# design.net
KiCad netlist of a schematic drawn in Altium Designer
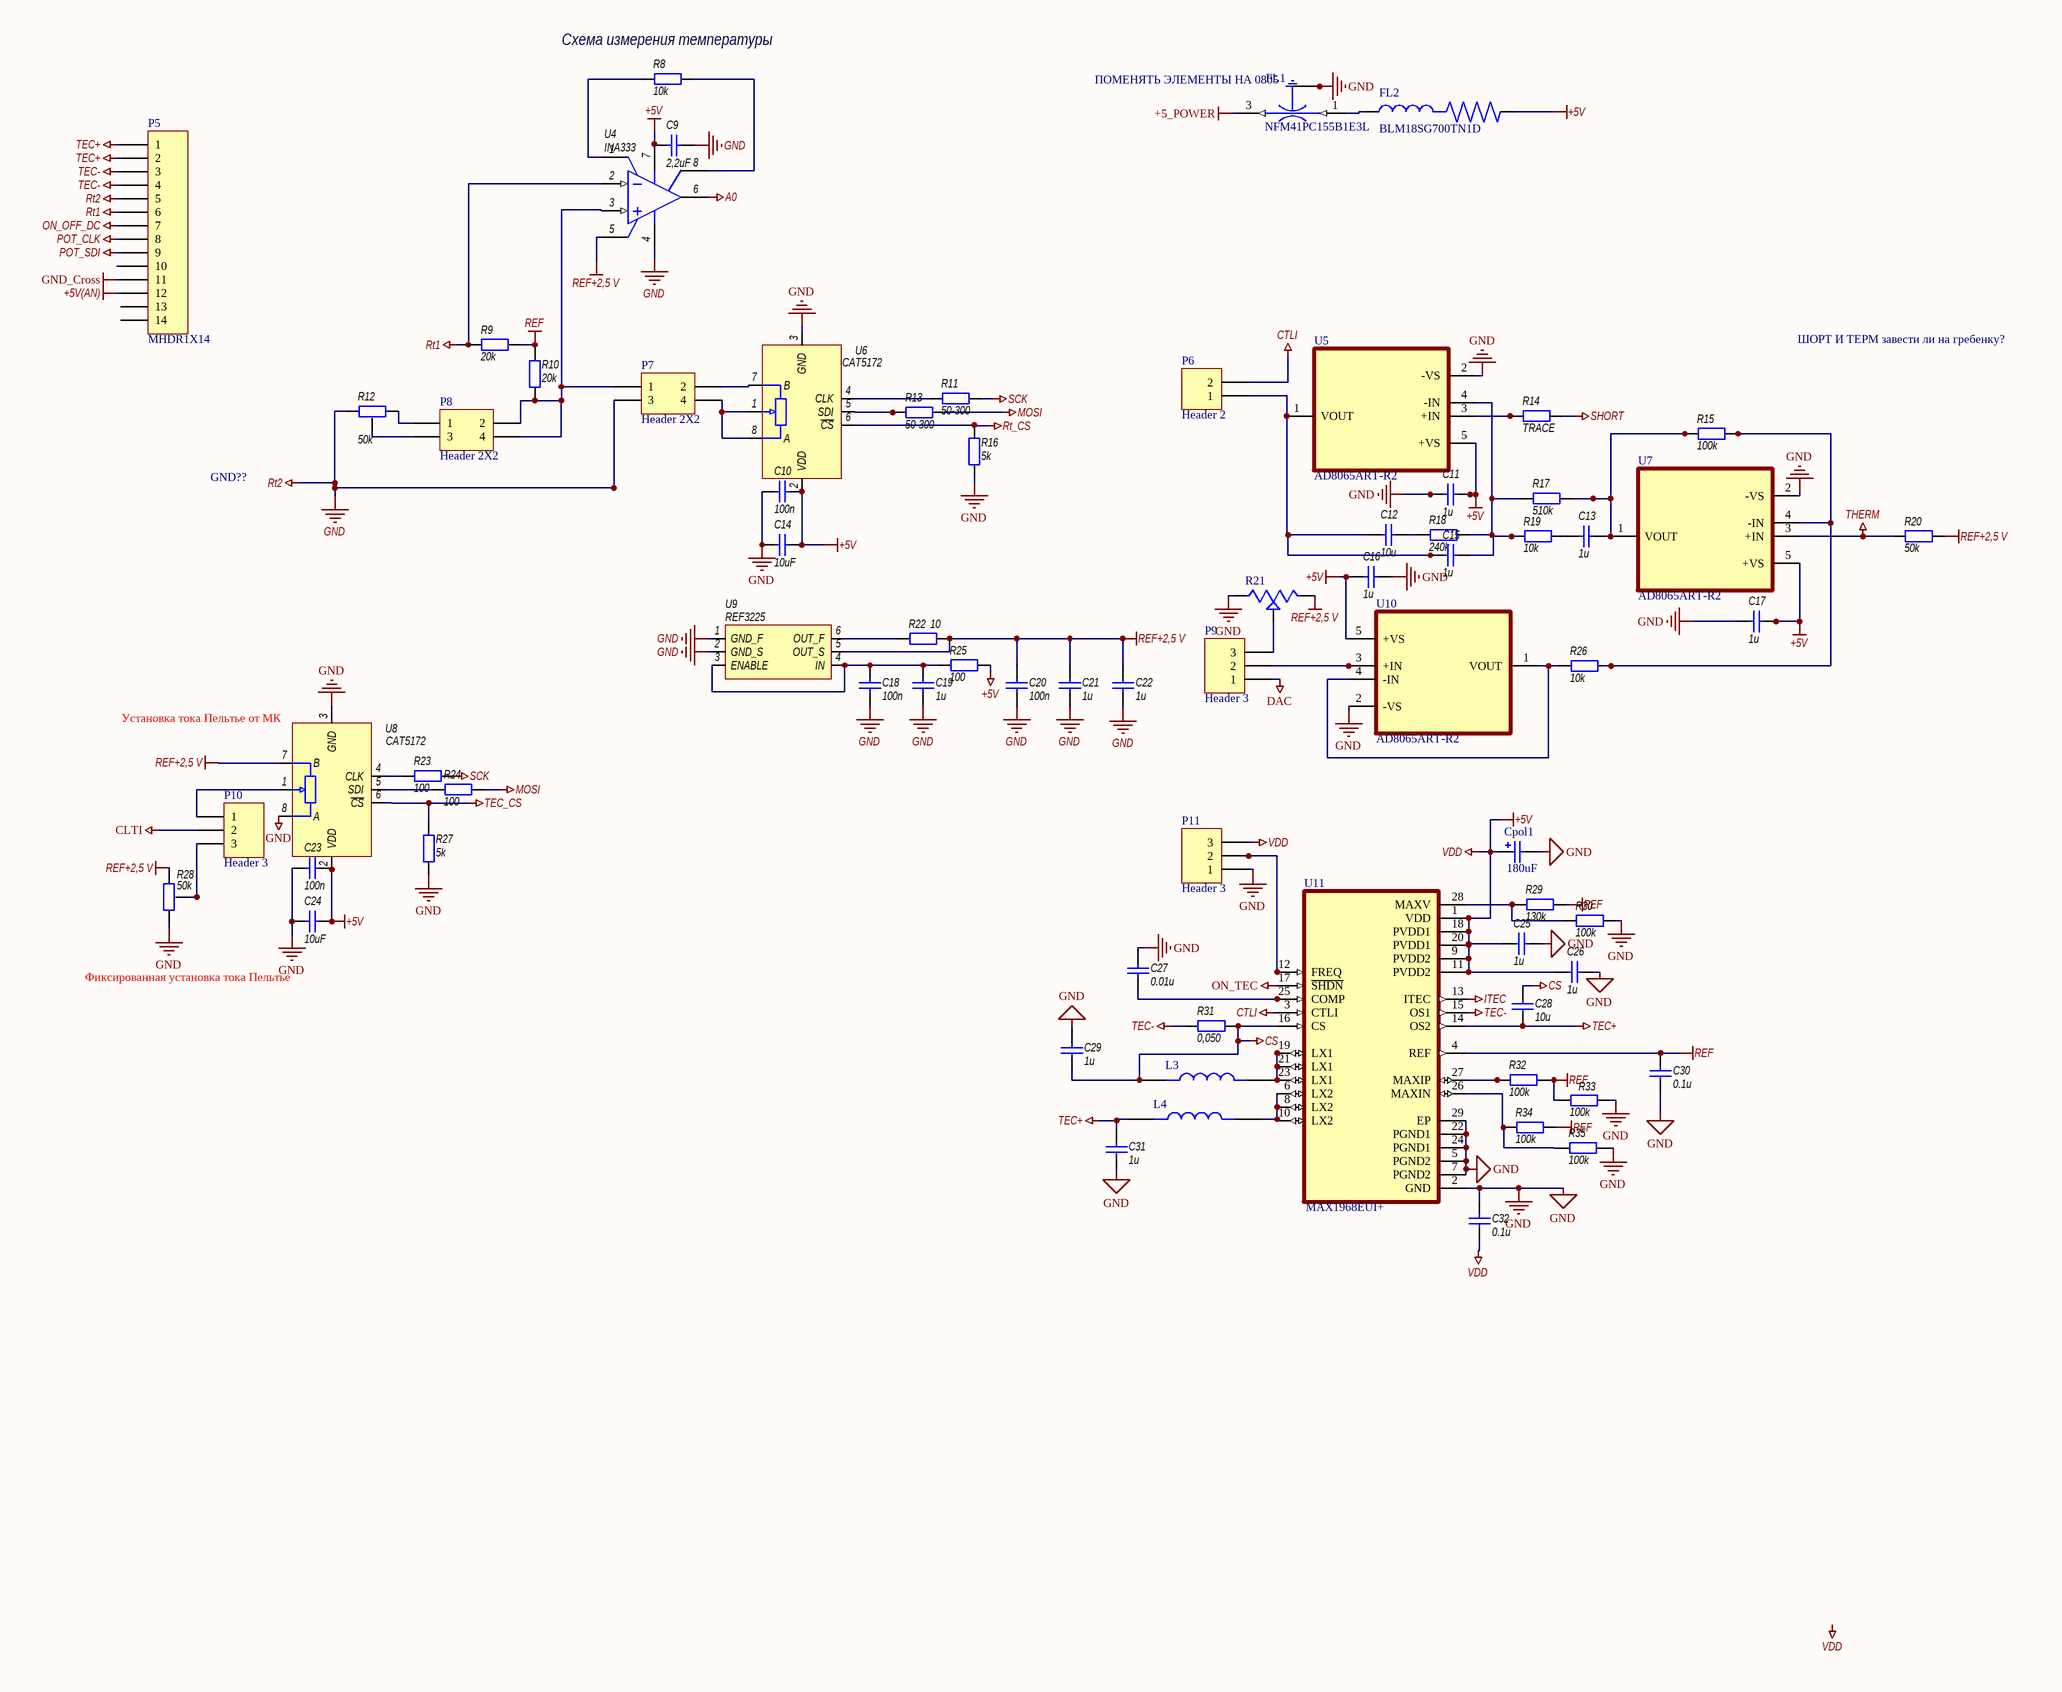
[diagram p0: схема платы пельтье.SchDoc]

(export (version "E")
  (design (tool "Eeschema 10.0.6"))
  (components
    (comp (ref "C9") (value "2,2uF") (footprint "0603") (libsource (lib "my-lib") (part "_capacitor")))
    (comp (ref "C10") (value "100n") (footprint "0603") (libsource (lib "my-lib") (part "_capacitor")))
    (comp (ref "C11") (value "1u") (footprint "0603") (libsource (lib "my-lib") (part "_capacitor")))
    (comp (ref "C12") (value "10u") (footprint "0603") (libsource (lib "my-lib") (part "_capacitor")))
    (comp (ref "C13") (value "1u") (footprint "0603") (libsource (lib "my-lib") (part "_capacitor")))
    (comp (ref "C14") (value "10uF") (footprint "0603") (libsource (lib "my-lib") (part "_capacitor")))
    (comp (ref "C15") (value "1u") (footprint "0603") (libsource (lib "my-lib") (part "_capacitor")))
    (comp (ref "C16") (value "1u") (footprint "0603") (libsource (lib "my-lib") (part "_capacitor")))
    (comp (ref "C17") (value "1u") (footprint "0603") (libsource (lib "my-lib") (part "_capacitor")))
    (comp (ref "C18") (value "100n") (footprint "0603") (libsource (lib "my-lib") (part "_capacitor")))
    (comp (ref "C19") (value "1u") (footprint "0603") (libsource (lib "my-lib") (part "_capacitor")))
    (comp (ref "C20") (value "100n") (footprint "0603") (libsource (lib "my-lib") (part "_capacitor")))
    (comp (ref "C21") (value "1u") (footprint "0603") (libsource (lib "my-lib") (part "_capacitor")))
    (comp (ref "C22") (value "1u") (footprint "0603") (libsource (lib "my-lib") (part "_capacitor")))
    (comp (ref "C23") (value "100n") (footprint "0603") (libsource (lib "my-lib") (part "_capacitor")))
    (comp (ref "C24") (value "10uF") (footprint "0603") (libsource (lib "my-lib") (part "_capacitor")))
    (comp (ref "C25") (value "1u") (footprint "0603") (libsource (lib "my-lib") (part "_capacitor")))
    (comp (ref "C26") (value "1u") (footprint "0603") (libsource (lib "my-lib") (part "_capacitor")))
    (comp (ref "C27") (value "0.01u") (footprint "0603") (libsource (lib "my-lib") (part "_capacitor")))
    (comp (ref "C28") (value "10u") (footprint "0603") (libsource (lib "my-lib") (part "_capacitor")))
    (comp (ref "C29") (value "1u") (footprint "0603") (libsource (lib "my-lib") (part "_capacitor")))
    (comp (ref "C30") (value "0.1u") (footprint "0603") (libsource (lib "my-lib") (part "_capacitor")))
    (comp (ref "C31") (value "1u") (footprint "0603") (libsource (lib "my-lib") (part "_capacitor")))
    (comp (ref "C32") (value "0.1u") (footprint "0603") (libsource (lib "my-lib") (part "_capacitor")))
    (comp (ref "Cpol1")
      (value "180uF")
      (footprint "CAPPM7343X310N")
      (description "Polarized Capacitor (Axial)")
      (fields (field (name "PUBLISHER") "Altium Limited"))
      (libsource (lib "Miscellaneous Devices") (part "Cap Pol2"))
    )
    (comp (ref "FL1")
      (value "NFM41PC155B1E3L")
      (footprint "FIL_NFM41PC155B1E3L")
      (fields (field (name "MF") "Murata"))
      (libsource (lib "NFM41PC155B1E3L") (part "NFM41PC155B1E3L"))
    )
    (comp (ref "FL2")
      (value "BLM18SG700TN1D")
      (footprint "BEADC2012X105N")
      (fields (field (name "MF") "Murata") (field (name "MP") "BLM21SP111SN1D"))
      (libsource (lib "BLM21SP111SN1D") (part "BLM21SP111SN1D"))
    )
    (comp (ref "L3")
      (value "~")
      (footprint "IHLP")
      (description "Ð˜Ð½Ð´ÑƒÐºÑ‚Ð¾Ñ€ Ñ Ð¸Ð½Ð´ÑƒÐºÑ‚Ð¸Ð²Ð½Ð¾ÑÑ‚ÑŒÑŽ: 3,3 uH Tol. + / -30%, Ð¿Ð°ÐºÐµÑ‚: 2020 (5050)")
      (fields (field (name "MF") "Murata") (field (name "MP") "LQH5BPN3R3NT0L"))
      (libsource (lib "LQH5BPN3R3NT0L") (part "LQH5BPN3R3NT0L"))
    )
    (comp (ref "L4")
      (value "~")
      (footprint "IHLP")
      (description "Ð˜Ð½Ð´ÑƒÐºÑ‚Ð¾Ñ€ Ñ Ð¸Ð½Ð´ÑƒÐºÑ‚Ð¸Ð²Ð½Ð¾ÑÑ‚ÑŒÑŽ: 3,3 uH Tol. + / -30%, Ð¿Ð°ÐºÐµÑ‚: 2020 (5050)")
      (fields (field (name "MF") "Murata") (field (name "MP") "LQH5BPN3R3NT0L"))
      (libsource (lib "LQH5BPN3R3NT0L") (part "LQH5BPN3R3NT0L"))
    )
    (comp (ref "P5")
      (value "MHDR1X14")
      (footprint "HDR1X14")
      (description "Header, 14-Pin")
      (fields (field (name "PUBLISHER") "Altium Limited"))
      (libsource (lib "Miscellaneous Connectors") (part "MHDR1X14"))
    )
    (comp (ref "P6")
      (value "Header 2")
      (footprint "HDR1X2")
      (description "Header, 2-Pin")
      (fields (field (name "PUBLISHER") "Altium Limited"))
      (libsource (lib "Miscellaneous Connectors") (part "Header 2"))
    )
    (comp (ref "P7")
      (value "Header 2X2")
      (footprint "HDR2X2")
      (description "Header, 2-Pin, Dual row")
      (fields (field (name "PUBLISHER") "Altium Limited"))
      (libsource (lib "Miscellaneous Connectors") (part "Header 2X2"))
    )
    (comp (ref "P8")
      (value "Header 2X2")
      (footprint "HDR2X2")
      (description "Header, 2-Pin, Dual row")
      (fields (field (name "PUBLISHER") "Altium Limited"))
      (libsource (lib "Miscellaneous Connectors") (part "Header 2X2"))
    )
    (comp (ref "P9")
      (value "Header 3")
      (footprint "HDR1X3")
      (description "Header, 3-Pin")
      (fields (field (name "PUBLISHER") "Altium Limited"))
      (libsource (lib "Miscellaneous Connectors") (part "Header 3"))
    )
    (comp (ref "P10")
      (value "Header 3")
      (footprint "HDR1X3")
      (description "Header, 3-Pin")
      (fields (field (name "PUBLISHER") "Altium Limited"))
      (libsource (lib "") (part "Header 3_1"))
    )
    (comp (ref "P11")
      (value "Header 3")
      (footprint "HDR1X3")
      (description "Header, 3-Pin")
      (fields (field (name "PUBLISHER") "Altium Limited"))
      (libsource (lib "Miscellaneous Connectors") (part "Header 3"))
    )
    (comp (ref "R8") (value "10k") (footprint "0603") (libsource (lib "my-lib") (part "_resistor")))
    (comp (ref "R9") (value "20k") (footprint "0603") (libsource (lib "my-lib") (part "_resistor")))
    (comp (ref "R10") (value "20k") (footprint "0603") (libsource (lib "my-lib") (part "_resistor")))
    (comp (ref "R11") (value "50-300") (footprint "0603") (libsource (lib "my-lib") (part "_resistor")))
    (comp (ref "R12")
      (value "50k")
      (footprint "TRIM_3296X-1-203LF")
      (description "3224J")
      (libsource (lib "my-lib") (part "_resistor_pot"))
    )
    (comp (ref "R13") (value "50-300") (footprint "0603") (libsource (lib "my-lib") (part "_resistor")))
    (comp (ref "R14") (value "TRACE") (footprint "0603") (libsource (lib "my-lib") (part "_resistor")))
    (comp (ref "R15") (value "100k") (footprint "0603") (libsource (lib "my-lib") (part "_resistor")))
    (comp (ref "R16") (value "5k") (footprint "0603") (libsource (lib "my-lib") (part "_resistor")))
    (comp (ref "R17") (value "510k") (footprint "0603") (libsource (lib "my-lib") (part "_resistor")))
    (comp (ref "R18") (value "240k") (footprint "0603") (libsource (lib "my-lib") (part "_resistor")))
    (comp (ref "R19") (value "10k") (footprint "0603") (libsource (lib "my-lib") (part "_resistor")))
    (comp (ref "R20") (value "50k") (footprint "0603") (libsource (lib "my-lib") (part "_resistor")))
    (comp (ref "R21")
      (value "~")
      (footprint "TRIM_3296X-1-203LF")
      (description "Trimmer Resistors - Through Hole")
      (fields (field (name "MP") "3296W-1-224LF") (field (name "MF") "Bourns"))
      (libsource (lib "3296W-1-224LF") (part "3296W-1-224LF"))
    )
    (comp (ref "R22") (value "10") (footprint "0603") (libsource (lib "my-lib") (part "_resistor")))
    (comp (ref "R23") (value "100") (footprint "0603") (libsource (lib "my-lib") (part "_resistor")))
    (comp (ref "R24") (value "100") (footprint "0603") (libsource (lib "my-lib") (part "_resistor")))
    (comp (ref "R25") (value "100") (footprint "0603") (libsource (lib "my-lib") (part "_resistor")))
    (comp (ref "R26") (value "10k") (footprint "0603") (libsource (lib "my-lib") (part "_resistor")))
    (comp (ref "R27") (value "5k") (footprint "0603") (libsource (lib "my-lib") (part "_resistor")))
    (comp (ref "R28")
      (value "50k")
      (footprint "TRIM_3296X-1-203LF")
      (description "3224J")
      (libsource (lib "my-lib") (part "_resistor_pot"))
    )
    (comp (ref "R29") (value "130k") (footprint "0603") (libsource (lib "my-lib") (part "_resistor")))
    (comp (ref "R30") (value "100k") (footprint "0603") (libsource (lib "my-lib") (part "_resistor")))
    (comp (ref "R31")
      (value "0,050")
      (footprint "RESC3216X65N")
      (libsource (lib "my-lib") (part "_resistor"))
    )
    (comp (ref "R32") (value "100k") (footprint "0603") (libsource (lib "my-lib") (part "_resistor")))
    (comp (ref "R33") (value "100k") (footprint "0603") (libsource (lib "my-lib") (part "_resistor")))
    (comp (ref "R34") (value "100k") (footprint "0603") (libsource (lib "my-lib") (part "_resistor")))
    (comp (ref "R35") (value "100k") (footprint "0603") (libsource (lib "my-lib") (part "_resistor")))
    (comp (ref "U4")
      (value "INA333")
      (footprint "SOP65P490X110-8N")
      (libsource (lib "my-lib") (part "INA333"))
    )
    (comp (ref "U5")
      (value "AD8065ART-R2")
      (footprint "SOT95P290X145-5N")
      (fields (field (name "MF") "Analog Devices"))
      (libsource (lib "AD8065ART-R2") (part "AD8065ART-R2"))
    )
    (comp (ref "U6")
      (value "CAT5172")
      (footprint "SOT65P280X100-8N")
      (description "Digital potentiometr 256-position SPI")
      (libsource (lib "my-lib") (part "CAT5172"))
    )
    (comp (ref "U7")
      (value "AD8065ART-R2")
      (footprint "SOT95P290X145-5N")
      (fields (field (name "MF") "Analog Devices"))
      (libsource (lib "AD8065ART-R2") (part "AD8065ART-R2"))
    )
    (comp (ref "U8")
      (value "CAT5172")
      (footprint "SOT65P280X100-8N")
      (description "Digital potentiometr 256-position SPI")
      (libsource (lib "my-lib") (part "CAT5172"))
    )
    (comp (ref "U9")
      (value "REF3225")
      (footprint "SOT23-6")
      (description "SERIES VOLTAGE REFERENCE")
      (libsource (lib "my-lib") (part "REF32XX"))
    )
    (comp (ref "U10")
      (value "AD8065ART-R2")
      (footprint "SOT95P290X145-5N")
      (fields (field (name "MF") "Analog Devices"))
      (libsource (lib "") (part "AD8065ART-R2_1"))
    )
    (comp (ref "U11")
      (value "MAX1968EUI+")
      (footprint "SOP65P637X110-29N")
      (description "Thermoelectric Cooler PMIC 28-TSSOP-EP")
      (fields (field (name "MF") "Maxim Integrated"))
      (libsource (lib "MAX1968EUI_") (part "MAX1968EUI+"))
    )
  )
  (nets
    (net (code "1") (name "+5V") (class "Default")
      (node (ref "C10") (pin "2") (pinfunction "2_2") (pintype "passive"))
      (node (ref "C11") (pin "2") (pinfunction "2_2") (pintype "passive"))
      (node (ref "C14") (pin "2") (pinfunction "2_2") (pintype "passive"))
      (node (ref "C16") (pin "1") (pinfunction "1_1") (pintype "passive"))
      (node (ref "C17") (pin "2") (pinfunction "2_2") (pintype "passive"))
      (node (ref "C23") (pin "2") (pinfunction "2_2") (pintype "passive"))
      (node (ref "C24") (pin "2") (pinfunction "2_2") (pintype "passive"))
      (node (ref "C25") (pin "1") (pinfunction "1_1") (pintype "passive"))
      (node (ref "C26") (pin "1") (pinfunction "1_1") (pintype "passive"))
      (node (ref "C32") (pin "2") (pinfunction "2_2") (pintype "passive"))
      (node (ref "C9") (pin "2") (pinfunction "2_2") (pintype "passive"))
      (node (ref "Cpol1") (pin "1") (pinfunction "1_1") (pintype "passive"))
      (node (ref "FL2") (pin "2") (pinfunction "2_2") (pintype "passive"))
      (node (ref "P11") (pin "3") (pinfunction "3_3") (pintype "passive"))
      (node (ref "R25") (pin "2") (pinfunction "2_2") (pintype "passive"))
      (node (ref "U10") (pin "5") (pinfunction "+VS_5") (pintype "power_in"))
      (node (ref "U11") (pin "1") (pinfunction "VDD_1") (pintype "power_in"))
      (node (ref "U11") (pin "11") (pinfunction "PVDD2_11") (pintype "power_in"))
      (node (ref "U11") (pin "18") (pinfunction "PVDD1_18") (pintype "power_in"))
      (node (ref "U11") (pin "20") (pinfunction "PVDD1_20") (pintype "power_in"))
      (node (ref "U11") (pin "9") (pinfunction "PVDD2_9") (pintype "power_in"))
      (node (ref "U4") (pin "7") (pinfunction "V+_7") (pintype "power_in"))
      (node (ref "U5") (pin "5") (pinfunction "+VS_5") (pintype "power_in"))
      (node (ref "U6") (pin "2") (pinfunction "VDD_2") (pintype "passive"))
      (node (ref "U7") (pin "5") (pinfunction "+VS_5") (pintype "power_in"))
      (node (ref "U8") (pin "2") (pinfunction "VDD_2") (pintype "passive"))
    )
    (net (code "2") (name "+5V(AN)") (class "Default")
      (node (ref "P5") (pin "12") (pinfunction "12_12") (pintype "passive"))
    )
    (net (code "3") (name "+5_POWER") (class "Default")
      (node (ref "FL1") (pin "3") (pinfunction "OUT_3") (pintype "output"))
    )
    (net (code "4") (name "A0") (class "Default")
      (node (ref "U4") (pin "6") (pinfunction "OUT_6") (pintype "open_collector"))
    )
    (net (code "5") (name "CLTI") (class "Default")
      (node (ref "P10") (pin "2") (pinfunction "2_2") (pintype "passive"))
    )
    (net (code "6") (name "CS") (class "Default")
      (node (ref "C28") (pin "1") (pinfunction "1_1") (pintype "passive"))
      (node (ref "C29") (pin "2") (pinfunction "2_2") (pintype "passive"))
      (node (ref "L3") (pin "1") (pinfunction "1_1") (pintype "passive"))
      (node (ref "R31") (pin "2") (pinfunction "2_2") (pintype "passive"))
      (node (ref "U11") (pin "16") (pinfunction "CS_16") (pintype "input"))
    )
    (net (code "7") (name "CTLI") (class "Default")
      (node (ref "P6") (pin "2") (pinfunction "2_2") (pintype "passive"))
      (node (ref "U11") (pin "3") (pinfunction "CTLI_3") (pintype "input"))
    )
    (net (code "8") (name "DAC") (class "Default")
      (node (ref "P9") (pin "1") (pinfunction "1_1") (pintype "passive"))
    )
    (net (code "9") (name "GND") (class "Default")
      (node (ref "C10") (pin "1") (pinfunction "1_1") (pintype "passive"))
      (node (ref "C11") (pin "1") (pinfunction "1_1") (pintype "passive"))
      (node (ref "C14") (pin "1") (pinfunction "1_1") (pintype "passive"))
      (node (ref "C16") (pin "2") (pinfunction "2_2") (pintype "passive"))
      (node (ref "C17") (pin "1") (pinfunction "1_1") (pintype "passive"))
      (node (ref "C18") (pin "2") (pinfunction "2_2") (pintype "passive"))
      (node (ref "C19") (pin "2") (pinfunction "2_2") (pintype "passive"))
      (node (ref "C20") (pin "2") (pinfunction "2_2") (pintype "passive"))
      (node (ref "C21") (pin "2") (pinfunction "2_2") (pintype "passive"))
      (node (ref "C22") (pin "2") (pinfunction "2_2") (pintype "passive"))
      (node (ref "C23") (pin "1") (pinfunction "1_1") (pintype "passive"))
      (node (ref "C24") (pin "1") (pinfunction "1_1") (pintype "passive"))
      (node (ref "C25") (pin "2") (pinfunction "2_2") (pintype "passive"))
      (node (ref "C26") (pin "2") (pinfunction "2_2") (pintype "passive"))
      (node (ref "C27") (pin "1") (pinfunction "1_1") (pintype "passive"))
      (node (ref "C29") (pin "1") (pinfunction "1_1") (pintype "passive"))
      (node (ref "C30") (pin "2") (pinfunction "2_2") (pintype "passive"))
      (node (ref "C31") (pin "2") (pinfunction "2_2") (pintype "passive"))
      (node (ref "C32") (pin "1") (pinfunction "1_1") (pintype "passive"))
      (node (ref "C9") (pin "1") (pinfunction "1_1") (pintype "passive"))
      (node (ref "Cpol1") (pin "2") (pinfunction "2_2") (pintype "passive"))
      (node (ref "FL1") (pin "2") (pinfunction "GND_2") (pintype "power_in"))
      (node (ref "FL1") (pin "2_1") (pinfunction "GND_2_1") (pintype "power_in"))
      (node (ref "FL1") (pin "2_3") (pinfunction "GND_2_3") (pintype "power_in"))
      (node (ref "FL1") (pin "2_4") (pinfunction "GND_2_4") (pintype "power_in"))
      (node (ref "P11") (pin "1") (pinfunction "1_1") (pintype "passive"))
      (node (ref "P5") (pin "5") (pinfunction "5_5") (pintype "passive"))
      (node (ref "P7") (pin "3") (pinfunction "3_3") (pintype "passive"))
      (node (ref "R12") (pin "3") (pinfunction "3_3") (pintype "passive"))
      (node (ref "R16") (pin "1") (pinfunction "1_1") (pintype "passive"))
      (node (ref "R21") (pin "1") (pinfunction "CCW_1") (pintype "passive"))
      (node (ref "R27") (pin "1") (pinfunction "1_1") (pintype "passive"))
      (node (ref "R28") (pin "3") (pinfunction "3_3") (pintype "passive"))
      (node (ref "R30") (pin "2") (pinfunction "2_2") (pintype "passive"))
      (node (ref "R33") (pin "2") (pinfunction "2_2") (pintype "passive"))
      (node (ref "R35") (pin "2") (pinfunction "2_2") (pintype "passive"))
      (node (ref "U10") (pin "2") (pinfunction "-VS_2") (pintype "power_in"))
      (node (ref "U11") (pin "2") (pinfunction "GND_2") (pintype "power_in"))
      (node (ref "U11") (pin "22") (pinfunction "PGND1_22") (pintype "power_in"))
      (node (ref "U11") (pin "24") (pinfunction "PGND1_24") (pintype "power_in"))
      (node (ref "U11") (pin "29") (pinfunction "EP_29") (pintype "passive"))
      (node (ref "U11") (pin "5") (pinfunction "PGND2_5") (pintype "power_in"))
      (node (ref "U11") (pin "7") (pinfunction "PGND2_7") (pintype "power_in"))
      (node (ref "U4") (pin "4") (pinfunction "V-_4") (pintype "power_in"))
      (node (ref "U5") (pin "2") (pinfunction "-VS_2") (pintype "power_in"))
      (node (ref "U6") (pin "3") (pinfunction "GND_3") (pintype "passive"))
      (node (ref "U7") (pin "2") (pinfunction "-VS_2") (pintype "power_in"))
      (node (ref "U8") (pin "3") (pinfunction "GND_3") (pintype "passive"))
      (node (ref "U8") (pin "8") (pinfunction "A_8") (pintype "passive"))
      (node (ref "U9") (pin "1") (pinfunction "GND_F_1") (pintype "passive"))
      (node (ref "U9") (pin "2") (pinfunction "GND_S_2") (pintype "passive"))
    )
    (net (code "10") (name "GND_Cross") (class "Default")
      (node (ref "P5") (pin "11") (pinfunction "11_11") (pintype "passive"))
    )
    (net (code "11") (name "ITEC") (class "Default")
      (node (ref "U11") (pin "13") (pinfunction "ITEC_13") (pintype "output"))
    )
    (net (code "12") (name "MOSI") (class "Default")
      (node (ref "R13") (pin "2") (pinfunction "2_2") (pintype "passive"))
      (node (ref "R24") (pin "2") (pinfunction "2_2") (pintype "passive"))
    )
    (net (code "13") (name "Net-(C12-Pad2)") (class "Default")
      (node (ref "C12") (pin "2") (pinfunction "2_2") (pintype "passive"))
      (node (ref "R18") (pin "1") (pinfunction "1_1") (pintype "passive"))
    )
    (net (code "14") (name "Net-(C13-Pad1)") (class "Default")
      (node (ref "C13") (pin "1") (pinfunction "1_1") (pintype "passive"))
      (node (ref "R19") (pin "2") (pinfunction "2_2") (pintype "passive"))
    )
    (net (code "15") (name "Net-(FL1-IN)") (class "Default")
      (node (ref "FL1") (pin "1") (pinfunction "IN_1") (pintype "input"))
      (node (ref "FL2") (pin "1") (pinfunction "1_1") (pintype "passive"))
    )
    (net (code "16") (name "Net-(L3-Pad2)") (class "Default")
      (node (ref "L3") (pin "2") (pinfunction "2_2") (pintype "passive"))
      (node (ref "U11") (pin "19") (pinfunction "LX1_19") (pintype "bidirectional"))
      (node (ref "U11") (pin "21") (pinfunction "LX1_21") (pintype "bidirectional"))
      (node (ref "U11") (pin "23") (pinfunction "LX1_23") (pintype "bidirectional"))
    )
    (net (code "17") (name "Net-(L4-Pad2)") (class "Default")
      (node (ref "L4") (pin "2") (pinfunction "2_2") (pintype "passive"))
      (node (ref "U11") (pin "10") (pinfunction "LX2_10") (pintype "bidirectional"))
      (node (ref "U11") (pin "6") (pinfunction "LX2_6") (pintype "bidirectional"))
      (node (ref "U11") (pin "8") (pinfunction "LX2_8") (pintype "bidirectional"))
    )
    (net (code "18") (name "Net-(P8-Pad1)") (class "Default")
      (node (ref "P8") (pin "1") (pinfunction "1_1") (pintype "passive"))
      (node (ref "R12") (pin "1") (pinfunction "1_1") (pintype "passive"))
    )
    (net (code "19") (name "Net-(P8-Pad3)") (class "Default")
      (node (ref "P8") (pin "3") (pinfunction "3_3") (pintype "passive"))
      (node (ref "R12") (pin "2") (pinfunction "2_2") (pintype "passive"))
    )
    (net (code "20") (name "Net-(P10-Pad1)") (class "Default")
      (node (ref "P10") (pin "1") (pinfunction "1_1") (pintype "passive"))
      (node (ref "U8") (pin "1") (pintype "passive"))
    )
    (net (code "21") (name "Net-(P10-Pad3)") (class "Default")
      (node (ref "P10") (pin "3") (pinfunction "3_3") (pintype "passive"))
      (node (ref "R28") (pin "2") (pinfunction "2_2") (pintype "passive"))
    )
    (net (code "22") (name "Net-(R8-Pad1)") (class "Default")
      (node (ref "R8") (pin "1") (pinfunction "1_1") (pintype "passive"))
      (node (ref "U4") (pin "1") (pinfunction "RG_1") (pintype "power_in"))
    )
    (net (code "23") (name "Net-(R8-Pad2)") (class "Default")
      (node (ref "R8") (pin "2") (pinfunction "2_2") (pintype "passive"))
      (node (ref "U4") (pin "8") (pinfunction "RG_8") (pintype "power_in"))
    )
    (net (code "24") (name "Net-(R21-WIPER)") (class "Default")
      (node (ref "P9") (pin "3") (pinfunction "3_3") (pintype "passive"))
      (node (ref "R21") (pin "2") (pinfunction "WIPER_2") (pintype "passive"))
    )
    (net (code "25") (name "Net-(U4-IN+)") (class "Default")
      (node (ref "P7") (pin "1") (pinfunction "1_1") (pintype "passive"))
      (node (ref "P8") (pin "2") (pinfunction "2_2") (pintype "passive"))
      (node (ref "P8") (pin "4") (pinfunction "4_4") (pintype "passive"))
      (node (ref "R10") (pin "1") (pinfunction "1_1") (pintype "passive"))
      (node (ref "U4") (pin "3") (pinfunction "IN+_3") (pintype "input"))
    )
    (net (code "26") (name "Net-(U5-+IN)") (class "Default")
      (node (ref "R14") (pin "1") (pinfunction "1_1") (pintype "passive"))
      (node (ref "U5") (pin "3") (pinfunction "+IN_3") (pintype "passive"))
    )
    (net (code "27") (name "Net-(U5--IN)") (class "Default")
      (node (ref "C15") (pin "2") (pinfunction "2_2") (pintype "passive"))
      (node (ref "R17") (pin "1") (pinfunction "1_1") (pintype "passive"))
      (node (ref "R18") (pin "2") (pinfunction "2_2") (pintype "passive"))
      (node (ref "R19") (pin "1") (pinfunction "1_1") (pintype "passive"))
      (node (ref "U5") (pin "4") (pinfunction "-IN_4") (pintype "passive"))
    )
    (net (code "28") (name "Net-(U5-VOUT)") (class "Default")
      (node (ref "C12") (pin "1") (pinfunction "1_1") (pintype "passive"))
      (node (ref "C15") (pin "1") (pinfunction "1_1") (pintype "passive"))
      (node (ref "P6") (pin "1") (pinfunction "1_1") (pintype "passive"))
      (node (ref "U5") (pin "1") (pinfunction "VOUT_1") (pintype "passive"))
    )
    (net (code "29") (name "Net-(U6-A)") (class "Default")
      (node (ref "P7") (pin "4") (pinfunction "4_4") (pintype "passive"))
      (node (ref "U6") (pin "1") (pintype "passive"))
      (node (ref "U6") (pin "8") (pinfunction "A_8") (pintype "passive"))
    )
    (net (code "30") (name "Net-(U6-B)") (class "Default")
      (node (ref "P7") (pin "2") (pinfunction "2_2") (pintype "passive"))
      (node (ref "U6") (pin "7") (pinfunction "B_7") (pintype "passive"))
    )
    (net (code "31") (name "Net-(U6-CLK)") (class "Default")
      (node (ref "R11") (pin "1") (pinfunction "1_1") (pintype "passive"))
      (node (ref "U6") (pin "4") (pinfunction "CLK_4") (pintype "passive"))
    )
    (net (code "32") (name "Net-(U6-SDI)") (class "Default")
      (node (ref "R13") (pin "1") (pinfunction "1_1") (pintype "passive"))
      (node (ref "U6") (pin "5") (pinfunction "SDI_5") (pintype "passive"))
    )
    (net (code "33") (name "Net-(U7--IN)") (class "Default")
      (node (ref "R15") (pin "2") (pinfunction "2_2") (pintype "passive"))
      (node (ref "R26") (pin "2") (pinfunction "2_2") (pintype "passive"))
      (node (ref "U7") (pin "4") (pinfunction "-IN_4") (pintype "passive"))
    )
    (net (code "34") (name "Net-(U7-VOUT)") (class "Default")
      (node (ref "C13") (pin "2") (pinfunction "2_2") (pintype "passive"))
      (node (ref "R15") (pin "1") (pinfunction "1_1") (pintype "passive"))
      (node (ref "R17") (pin "2") (pinfunction "2_2") (pintype "passive"))
      (node (ref "U7") (pin "1") (pinfunction "VOUT_1") (pintype "passive"))
    )
    (net (code "35") (name "Net-(U8-CLK)") (class "Default")
      (node (ref "R23") (pin "1") (pinfunction "1_1") (pintype "passive"))
      (node (ref "U8") (pin "4") (pinfunction "CLK_4") (pintype "passive"))
    )
    (net (code "36") (name "Net-(U8-SDI)") (class "Default")
      (node (ref "R24") (pin "1") (pinfunction "1_1") (pintype "passive"))
      (node (ref "U8") (pin "5") (pinfunction "SDI_5") (pintype "passive"))
    )
    (net (code "37") (name "Net-(U9-ENABLE)") (class "Default")
      (node (ref "C18") (pin "1") (pinfunction "1_1") (pintype "passive"))
      (node (ref "C19") (pin "1") (pinfunction "1_1") (pintype "passive"))
      (node (ref "R25") (pin "1") (pinfunction "1_1") (pintype "passive"))
      (node (ref "U9") (pin "3") (pinfunction "ENABLE_3") (pintype "passive"))
      (node (ref "U9") (pin "4") (pinfunction "IN_4") (pintype "passive"))
    )
    (net (code "38") (name "Net-(U9-OUT_F)") (class "Default")
      (node (ref "R22") (pin "1") (pinfunction "1_1") (pintype "passive"))
      (node (ref "U9") (pin "6") (pinfunction "OUT_F_6") (pintype "passive"))
    )
    (net (code "39") (name "Net-(U10-+IN)") (class "Default")
      (node (ref "P9") (pin "2") (pinfunction "2_2") (pintype "passive"))
      (node (ref "U10") (pin "3") (pinfunction "+IN_3") (pintype "passive"))
    )
    (net (code "40") (name "Net-(U10--IN)") (class "Default")
      (node (ref "R26") (pin "1") (pinfunction "1_1") (pintype "passive"))
      (node (ref "U10") (pin "1") (pinfunction "VOUT_1") (pintype "passive"))
      (node (ref "U10") (pin "4") (pinfunction "-IN_4") (pintype "passive"))
    )
    (net (code "41") (name "Net-(U11-COMP)") (class "Default")
      (node (ref "C27") (pin "2") (pinfunction "2_2") (pintype "passive"))
      (node (ref "U11") (pin "25") (pinfunction "COMP_25") (pintype "input"))
    )
    (net (code "42") (name "Net-(U11-FREQ)") (class "Default")
      (node (ref "P11") (pin "2") (pinfunction "2_2") (pintype "passive"))
      (node (ref "U11") (pin "12") (pinfunction "FREQ_12") (pintype "input"))
    )
    (net (code "43") (name "Net-(U11-MAXIN)") (class "Default")
      (node (ref "R34") (pin "1") (pinfunction "1_1") (pintype "passive"))
      (node (ref "R35") (pin "1") (pinfunction "1_1") (pintype "passive"))
      (node (ref "U11") (pin "26") (pinfunction "MAXIN_26") (pintype "bidirectional"))
    )
    (net (code "44") (name "Net-(U11-MAXIP)") (class "Default")
      (node (ref "R32") (pin "1") (pinfunction "1_1") (pintype "passive"))
      (node (ref "U11") (pin "27") (pinfunction "MAXIP_27") (pintype "bidirectional"))
    )
    (net (code "45") (name "Net-(U11-MAXV)") (class "Default")
      (node (ref "R29") (pin "1") (pinfunction "1_1") (pintype "passive"))
      (node (ref "R30") (pin "1") (pinfunction "1_1") (pintype "passive"))
      (node (ref "U11") (pin "28") (pinfunction "MAXV_28") (pintype "power_in"))
    )
    (net (code "46") (name "ON_OFF_DC") (class "Default")
      (node (ref "P5") (pin "7") (pinfunction "7_7") (pintype "passive"))
    )
    (net (code "47") (name "ON_TEC") (class "Default")
      (node (ref "U11") (pin "17") (pinfunction "~{SHDN}_17") (pintype "input"))
    )
    (net (code "48") (name "POT_CLK") (class "Default")
      (node (ref "P5") (pin "8") (pinfunction "8_8") (pintype "passive"))
    )
    (net (code "49") (name "POT_SDI") (class "Default")
      (node (ref "P5") (pin "9") (pinfunction "9_9") (pintype "passive"))
    )
    (net (code "50") (name "REF") (class "Default")
      (node (ref "C30") (pin "1") (pinfunction "1_1") (pintype "passive"))
      (node (ref "R10") (pin "2") (pinfunction "2_2") (pintype "passive"))
      (node (ref "R29") (pin "2") (pinfunction "2_2") (pintype "passive"))
      (node (ref "R32") (pin "2") (pinfunction "2_2") (pintype "passive"))
      (node (ref "R33") (pin "1") (pinfunction "1_1") (pintype "passive"))
      (node (ref "R34") (pin "2") (pinfunction "2_2") (pintype "passive"))
      (node (ref "R9") (pin "2") (pinfunction "2_2") (pintype "passive"))
      (node (ref "U11") (pin "4") (pinfunction "REF_4") (pintype "output"))
    )
    (net (code "51") (name "REF+2,5 V") (class "Default")
      (node (ref "C20") (pin "1") (pinfunction "1_1") (pintype "passive"))
      (node (ref "C21") (pin "1") (pinfunction "1_1") (pintype "passive"))
      (node (ref "C22") (pin "1") (pinfunction "1_1") (pintype "passive"))
      (node (ref "R20") (pin "2") (pinfunction "2_2") (pintype "passive"))
      (node (ref "R21") (pin "3") (pinfunction "CW_3") (pintype "passive"))
      (node (ref "R22") (pin "2") (pinfunction "2_2") (pintype "passive"))
      (node (ref "R28") (pin "1") (pinfunction "1_1") (pintype "passive"))
      (node (ref "U4") (pin "5") (pinfunction "REF_5") (pintype "power_in"))
      (node (ref "U8") (pin "7") (pinfunction "B_7") (pintype "passive"))
      (node (ref "U9") (pin "5") (pinfunction "OUT_S_5") (pintype "passive"))
    )
    (net (code "52") (name "Rt1") (class "Default")
      (node (ref "P5") (pin "6") (pinfunction "6_6") (pintype "passive"))
      (node (ref "R9") (pin "1") (pinfunction "1_1") (pintype "passive"))
      (node (ref "U4") (pin "2") (pinfunction "IN-_2") (pintype "input"))
    )
    (net (code "53") (name "Rt_CS") (class "Default")
      (node (ref "R16") (pin "2") (pinfunction "2_2") (pintype "passive"))
      (node (ref "U6") (pin "6") (pinfunction "~{CS}_6") (pintype "passive"))
    )
    (net (code "54") (name "SCK") (class "Default")
      (node (ref "R11") (pin "2") (pinfunction "2_2") (pintype "passive"))
      (node (ref "R23") (pin "2") (pinfunction "2_2") (pintype "passive"))
    )
    (net (code "55") (name "SHORT") (class "Default")
      (node (ref "R14") (pin "2") (pinfunction "2_2") (pintype "passive"))
    )
    (net (code "56") (name "TEC+") (class "Default")
      (node (ref "C28") (pin "2") (pinfunction "2_2") (pintype "passive"))
      (node (ref "C31") (pin "1") (pinfunction "1_1") (pintype "passive"))
      (node (ref "L4") (pin "1") (pinfunction "1_1") (pintype "passive"))
      (node (ref "P5") (pin "1") (pinfunction "1_1") (pintype "passive"))
      (node (ref "P5") (pin "2") (pinfunction "2_2") (pintype "passive"))
      (node (ref "U11") (pin "14") (pinfunction "OS2_14") (pintype "output"))
    )
    (net (code "57") (name "TEC-") (class "Default")
      (node (ref "P5") (pin "3") (pinfunction "3_3") (pintype "passive"))
      (node (ref "P5") (pin "4") (pinfunction "4_4") (pintype "passive"))
      (node (ref "R31") (pin "1") (pinfunction "1_1") (pintype "passive"))
      (node (ref "U11") (pin "15") (pinfunction "OS1_15") (pintype "output"))
    )
    (net (code "58") (name "TEC_CS") (class "Default")
      (node (ref "R27") (pin "2") (pinfunction "2_2") (pintype "passive"))
      (node (ref "U8") (pin "6") (pinfunction "~{CS}_6") (pintype "passive"))
    )
    (net (code "59") (name "THERM") (class "Default")
      (node (ref "R20") (pin "1") (pinfunction "1_1") (pintype "passive"))
      (node (ref "U7") (pin "3") (pinfunction "+IN_3") (pintype "passive"))
    )
    (net (code "60") (name "unconnected-(P5-Pad10)") (class "Default")
      (node (ref "P5") (pin "10") (pinfunction "10_10") (pintype "passive"))
    )
    (net (code "61") (name "unconnected-(P5-Pad13)") (class "Default")
      (node (ref "P5") (pin "13") (pinfunction "13_13") (pintype "passive"))
    )
    (net (code "62") (name "unconnected-(P5-Pad14)") (class "Default")
      (node (ref "P5") (pin "14") (pinfunction "14_14") (pintype "passive"))
    )
  )
)
